# pcbschematics00.net
KiCad netlist of a schematic drawn in EasyEDA
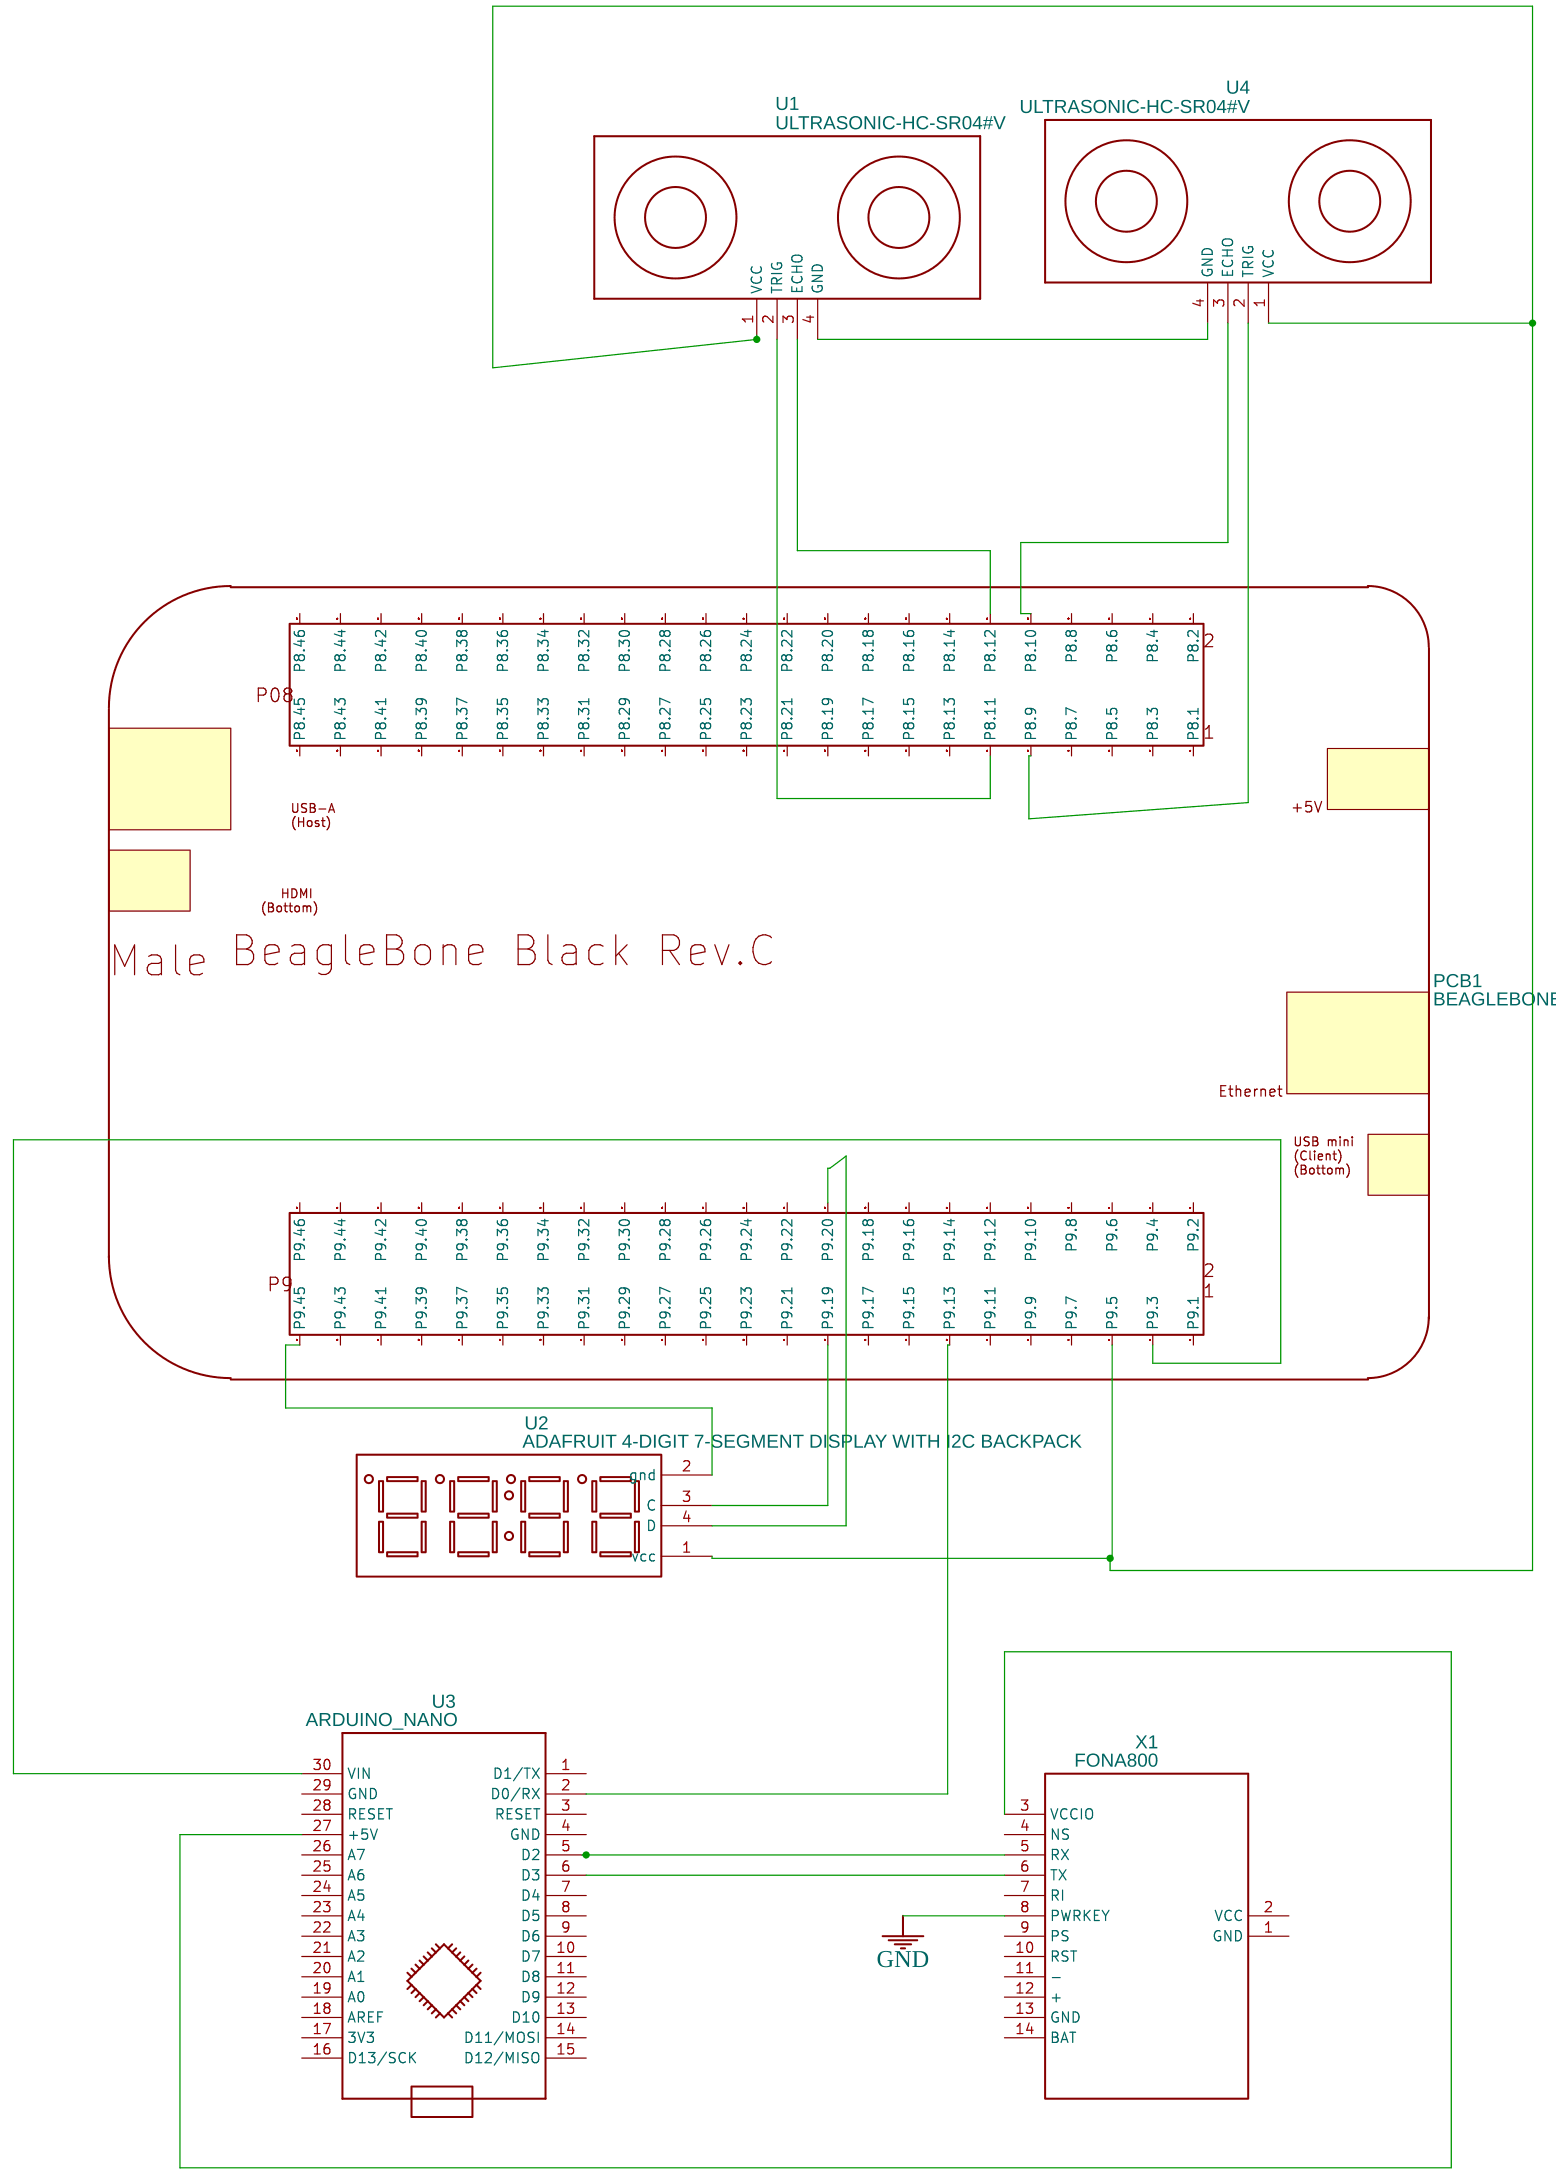
[diagram p0: schematic sheet]

(export (version "E")
  (design (tool "Eeschema 10.0.6"))
  (components
    (comp (ref "PCB1") (value "BEAGLEBONE_BLACK MALE") (libsource (lib "") (part "BEAGLEBONE_BLACK MALE")))
    (comp (ref "U1") (value "ULTRASONIC-HC-SR04#V") (libsource (lib "") (part "ULTRASONIC-HC-SR04#V")))
    (comp (ref "U2")
      (value "ADAFRUIT 4-DIGIT 7-SEGMENT DISPLAY WITH I2C BACKPACK")
      (libsource (lib "") (part "ADAFRUIT 4-DIGIT 7-SEGMENT DISPLAY WITH I2C BACKPACK"))
    )
    (comp (ref "U3") (value "ARDUINO_NANO") (libsource (lib "") (part "ARDUINO_NANO")))
    (comp (ref "U4") (value "ULTRASONIC-HC-SR04#V") (libsource (lib "") (part "ULTRASONIC-HC-SR04#V_1")))
    (comp (ref "X1") (value "FONA800") (libsource (lib "") (part "FONA800")))
  )
  (nets
    (net (code "1") (name "GND") (class "Default")
      (node (ref "X1") (pin "8") (pinfunction "PWRKEY_8") (pintype "unspecified"))
    )
    (net (code "2") (name "Net-(U1-ECHO)") (class "Default")
      (node (ref "PCB1") (pin "P8.12") (pinfunction "P8.12_P8.12") (pintype "bidirectional"))
      (node (ref "U1") (pin "3") (pinfunction "ECHO_3") (pintype "output"))
    )
    (net (code "3") (name "Net-(U1-GND)") (class "Default")
      (node (ref "U1") (pin "4") (pinfunction "GND_4") (pintype "passive"))
      (node (ref "U4") (pin "4") (pinfunction "GND_4") (pintype "passive"))
    )
    (net (code "4") (name "Net-(U1-TRIG)") (class "Default")
      (node (ref "PCB1") (pin "P8.11") (pinfunction "P8.11_P8.11") (pintype "bidirectional"))
      (node (ref "U1") (pin "2") (pinfunction "TRIG_2") (pintype "input"))
    )
    (net (code "5") (name "Net-(U1-VCC)") (class "Default")
      (node (ref "PCB1") (pin "P9.5") (pinfunction "P9.5_P9.5") (pintype "bidirectional"))
      (node (ref "U1") (pin "1") (pinfunction "VCC_1") (pintype "passive"))
      (node (ref "U2") (pin "1") (pinfunction "vcc_1") (pintype "unspecified"))
      (node (ref "U4") (pin "1") (pinfunction "VCC_1") (pintype "passive"))
    )
    (net (code "6") (name "Net-(U2-C)") (class "Default")
      (node (ref "PCB1") (pin "P9.19") (pinfunction "P9.19_P9.19") (pintype "bidirectional"))
      (node (ref "U2") (pin "3") (pinfunction "C_3") (pintype "unspecified"))
    )
    (net (code "7") (name "Net-(U2-D)") (class "Default")
      (node (ref "PCB1") (pin "P9.20") (pinfunction "P9.20_P9.20") (pintype "bidirectional"))
      (node (ref "U2") (pin "4") (pinfunction "D_4") (pintype "unspecified"))
    )
    (net (code "8") (name "Net-(U2-gnd)") (class "Default")
      (node (ref "PCB1") (pin "P9.45") (pinfunction "P9.45_P9.45") (pintype "bidirectional"))
      (node (ref "U2") (pin "2") (pinfunction "gnd_2") (pintype "unspecified"))
    )
    (net (code "9") (name "Net-(U3-+5V)") (class "Default")
      (node (ref "U3") (pin "27") (pinfunction "+5V_27") (pintype "unspecified"))
      (node (ref "X1") (pin "3") (pinfunction "VCCIO_3") (pintype "unspecified"))
    )
    (net (code "10") (name "Net-(U3-D0{slash}RX)") (class "Default")
      (node (ref "PCB1") (pin "P9.13") (pinfunction "P9.13_P9.13") (pintype "bidirectional"))
      (node (ref "U3") (pin "2") (pinfunction "D0/RX_2") (pintype "unspecified"))
    )
    (net (code "11") (name "Net-(U3-D2)") (class "Default")
      (node (ref "U3") (pin "5") (pinfunction "D2_5") (pintype "unspecified"))
      (node (ref "X1") (pin "5") (pinfunction "RX_5") (pintype "unspecified"))
    )
    (net (code "12") (name "Net-(U3-D3)") (class "Default")
      (node (ref "U3") (pin "6") (pinfunction "D3_6") (pintype "unspecified"))
      (node (ref "X1") (pin "6") (pinfunction "TX_6") (pintype "unspecified"))
    )
    (net (code "13") (name "Net-(U3-VIN)") (class "Default")
      (node (ref "PCB1") (pin "P9.3") (pinfunction "P9.3_P9.3") (pintype "bidirectional"))
      (node (ref "U3") (pin "30") (pinfunction "VIN_30") (pintype "unspecified"))
    )
    (net (code "14") (name "Net-(U4-ECHO)") (class "Default")
      (node (ref "PCB1") (pin "P8.10") (pinfunction "P8.10_P8.10") (pintype "bidirectional"))
      (node (ref "U4") (pin "3") (pinfunction "ECHO_3") (pintype "output"))
    )
    (net (code "15") (name "Net-(U4-TRIG)") (class "Default")
      (node (ref "PCB1") (pin "P8.9") (pinfunction "P8.9_P8.9") (pintype "bidirectional"))
      (node (ref "U4") (pin "2") (pinfunction "TRIG_2") (pintype "input"))
    )
    (net (code "16") (name "unconnected-(PCB1-PadP8.1)") (class "Default")
      (node (ref "PCB1") (pin "P8.1") (pinfunction "P8.1_P8.1") (pintype "bidirectional"))
    )
    (net (code "17") (name "unconnected-(PCB1-PadP8.2)") (class "Default")
      (node (ref "PCB1") (pin "P8.2") (pinfunction "P8.2_P8.2") (pintype "bidirectional"))
    )
    (net (code "18") (name "unconnected-(PCB1-PadP8.3)") (class "Default")
      (node (ref "PCB1") (pin "P8.3") (pinfunction "P8.3_P8.3") (pintype "bidirectional"))
    )
    (net (code "19") (name "unconnected-(PCB1-PadP8.4)") (class "Default")
      (node (ref "PCB1") (pin "P8.4") (pinfunction "P8.4_P8.4") (pintype "bidirectional"))
    )
    (net (code "20") (name "unconnected-(PCB1-PadP8.5)") (class "Default")
      (node (ref "PCB1") (pin "P8.5") (pinfunction "P8.5_P8.5") (pintype "bidirectional"))
    )
    (net (code "21") (name "unconnected-(PCB1-PadP8.6)") (class "Default")
      (node (ref "PCB1") (pin "P8.6") (pinfunction "P8.6_P8.6") (pintype "bidirectional"))
    )
    (net (code "22") (name "unconnected-(PCB1-PadP8.7)") (class "Default")
      (node (ref "PCB1") (pin "P8.7") (pinfunction "P8.7_P8.7") (pintype "bidirectional"))
    )
    (net (code "23") (name "unconnected-(PCB1-PadP8.8)") (class "Default")
      (node (ref "PCB1") (pin "P8.8") (pinfunction "P8.8_P8.8") (pintype "bidirectional"))
    )
    (net (code "24") (name "unconnected-(PCB1-PadP8.13)") (class "Default")
      (node (ref "PCB1") (pin "P8.13") (pinfunction "P8.13_P8.13") (pintype "bidirectional"))
    )
    (net (code "25") (name "unconnected-(PCB1-PadP8.14)") (class "Default")
      (node (ref "PCB1") (pin "P8.14") (pinfunction "P8.14_P8.14") (pintype "bidirectional"))
    )
    (net (code "26") (name "unconnected-(PCB1-PadP8.15)") (class "Default")
      (node (ref "PCB1") (pin "P8.15") (pinfunction "P8.15_P8.15") (pintype "bidirectional"))
    )
    (net (code "27") (name "unconnected-(PCB1-PadP8.16)") (class "Default")
      (node (ref "PCB1") (pin "P8.16") (pinfunction "P8.16_P8.16") (pintype "bidirectional"))
    )
    (net (code "28") (name "unconnected-(PCB1-PadP8.17)") (class "Default")
      (node (ref "PCB1") (pin "P8.17") (pinfunction "P8.17_P8.17") (pintype "bidirectional"))
    )
    (net (code "29") (name "unconnected-(PCB1-PadP8.18)") (class "Default")
      (node (ref "PCB1") (pin "P8.18") (pinfunction "P8.18_P8.18") (pintype "bidirectional"))
    )
    (net (code "30") (name "unconnected-(PCB1-PadP8.19)") (class "Default")
      (node (ref "PCB1") (pin "P8.19") (pinfunction "P8.19_P8.19") (pintype "bidirectional"))
    )
    (net (code "31") (name "unconnected-(PCB1-PadP8.20)") (class "Default")
      (node (ref "PCB1") (pin "P8.20") (pinfunction "P8.20_P8.20") (pintype "bidirectional"))
    )
    (net (code "32") (name "unconnected-(PCB1-PadP8.21)") (class "Default")
      (node (ref "PCB1") (pin "P8.21") (pinfunction "P8.21_P8.21") (pintype "bidirectional"))
    )
    (net (code "33") (name "unconnected-(PCB1-PadP8.22)") (class "Default")
      (node (ref "PCB1") (pin "P8.22") (pinfunction "P8.22_P8.22") (pintype "bidirectional"))
    )
    (net (code "34") (name "unconnected-(PCB1-PadP8.23)") (class "Default")
      (node (ref "PCB1") (pin "P8.23") (pinfunction "P8.23_P8.23") (pintype "bidirectional"))
    )
    (net (code "35") (name "unconnected-(PCB1-PadP8.24)") (class "Default")
      (node (ref "PCB1") (pin "P8.24") (pinfunction "P8.24_P8.24") (pintype "bidirectional"))
    )
    (net (code "36") (name "unconnected-(PCB1-PadP8.25)") (class "Default")
      (node (ref "PCB1") (pin "P8.25") (pinfunction "P8.25_P8.25") (pintype "bidirectional"))
    )
    (net (code "37") (name "unconnected-(PCB1-PadP8.26)") (class "Default")
      (node (ref "PCB1") (pin "P8.26") (pinfunction "P8.26_P8.26") (pintype "bidirectional"))
    )
    (net (code "38") (name "unconnected-(PCB1-PadP8.27)") (class "Default")
      (node (ref "PCB1") (pin "P8.27") (pinfunction "P8.27_P8.27") (pintype "bidirectional"))
    )
    (net (code "39") (name "unconnected-(PCB1-PadP8.28)") (class "Default")
      (node (ref "PCB1") (pin "P8.28") (pinfunction "P8.28_P8.28") (pintype "bidirectional"))
    )
    (net (code "40") (name "unconnected-(PCB1-PadP8.29)") (class "Default")
      (node (ref "PCB1") (pin "P8.29") (pinfunction "P8.29_P8.29") (pintype "bidirectional"))
    )
    (net (code "41") (name "unconnected-(PCB1-PadP8.30)") (class "Default")
      (node (ref "PCB1") (pin "P8.30") (pinfunction "P8.30_P8.30") (pintype "bidirectional"))
    )
    (net (code "42") (name "unconnected-(PCB1-PadP8.31)") (class "Default")
      (node (ref "PCB1") (pin "P8.31") (pinfunction "P8.31_P8.31") (pintype "bidirectional"))
    )
    (net (code "43") (name "unconnected-(PCB1-PadP8.32)") (class "Default")
      (node (ref "PCB1") (pin "P8.32") (pinfunction "P8.32_P8.32") (pintype "bidirectional"))
    )
    (net (code "44") (name "unconnected-(PCB1-PadP8.33)") (class "Default")
      (node (ref "PCB1") (pin "P8.33") (pinfunction "P8.33_P8.33") (pintype "bidirectional"))
    )
    (net (code "45") (name "unconnected-(PCB1-PadP8.34)") (class "Default")
      (node (ref "PCB1") (pin "P8.34") (pinfunction "P8.34_P8.34") (pintype "bidirectional"))
    )
    (net (code "46") (name "unconnected-(PCB1-PadP8.35)") (class "Default")
      (node (ref "PCB1") (pin "P8.35") (pinfunction "P8.35_P8.35") (pintype "bidirectional"))
    )
    (net (code "47") (name "unconnected-(PCB1-PadP8.36)") (class "Default")
      (node (ref "PCB1") (pin "P8.36") (pinfunction "P8.36_P8.36") (pintype "bidirectional"))
    )
    (net (code "48") (name "unconnected-(PCB1-PadP8.37)") (class "Default")
      (node (ref "PCB1") (pin "P8.37") (pinfunction "P8.37_P8.37") (pintype "bidirectional"))
    )
    (net (code "49") (name "unconnected-(PCB1-PadP8.38)") (class "Default")
      (node (ref "PCB1") (pin "P8.38") (pinfunction "P8.38_P8.38") (pintype "bidirectional"))
    )
    (net (code "50") (name "unconnected-(PCB1-PadP8.39)") (class "Default")
      (node (ref "PCB1") (pin "P8.39") (pinfunction "P8.39_P8.39") (pintype "bidirectional"))
    )
    (net (code "51") (name "unconnected-(PCB1-PadP8.40)") (class "Default")
      (node (ref "PCB1") (pin "P8.40") (pinfunction "P8.40_P8.40") (pintype "bidirectional"))
    )
    (net (code "52") (name "unconnected-(PCB1-PadP8.41)") (class "Default")
      (node (ref "PCB1") (pin "P8.41") (pinfunction "P8.41_P8.41") (pintype "bidirectional"))
    )
    (net (code "53") (name "unconnected-(PCB1-PadP8.42)") (class "Default")
      (node (ref "PCB1") (pin "P8.42") (pinfunction "P8.42_P8.42") (pintype "bidirectional"))
    )
    (net (code "54") (name "unconnected-(PCB1-PadP8.43)") (class "Default")
      (node (ref "PCB1") (pin "P8.43") (pinfunction "P8.43_P8.43") (pintype "bidirectional"))
    )
    (net (code "55") (name "unconnected-(PCB1-PadP8.44)") (class "Default")
      (node (ref "PCB1") (pin "P8.44") (pinfunction "P8.44_P8.44") (pintype "bidirectional"))
    )
    (net (code "56") (name "unconnected-(PCB1-PadP8.45)") (class "Default")
      (node (ref "PCB1") (pin "P8.45") (pinfunction "P8.45_P8.45") (pintype "bidirectional"))
    )
    (net (code "57") (name "unconnected-(PCB1-PadP8.46)") (class "Default")
      (node (ref "PCB1") (pin "P8.46") (pinfunction "P8.46_P8.46") (pintype "bidirectional"))
    )
    (net (code "58") (name "unconnected-(PCB1-PadP9.1)") (class "Default")
      (node (ref "PCB1") (pin "P9.1") (pinfunction "P9.1_P9.1") (pintype "bidirectional"))
    )
    (net (code "59") (name "unconnected-(PCB1-PadP9.2)") (class "Default")
      (node (ref "PCB1") (pin "P9.2") (pinfunction "P9.2_P9.2") (pintype "bidirectional"))
    )
    (net (code "60") (name "unconnected-(PCB1-PadP9.4)") (class "Default")
      (node (ref "PCB1") (pin "P9.4") (pinfunction "P9.4_P9.4") (pintype "bidirectional"))
    )
    (net (code "61") (name "unconnected-(PCB1-PadP9.6)") (class "Default")
      (node (ref "PCB1") (pin "P9.6") (pinfunction "P9.6_P9.6") (pintype "bidirectional"))
    )
    (net (code "62") (name "unconnected-(PCB1-PadP9.7)") (class "Default")
      (node (ref "PCB1") (pin "P9.7") (pinfunction "P9.7_P9.7") (pintype "bidirectional"))
    )
    (net (code "63") (name "unconnected-(PCB1-PadP9.8)") (class "Default")
      (node (ref "PCB1") (pin "P9.8") (pinfunction "P9.8_P9.8") (pintype "bidirectional"))
    )
    (net (code "64") (name "unconnected-(PCB1-PadP9.9)") (class "Default")
      (node (ref "PCB1") (pin "P9.9") (pinfunction "P9.9_P9.9") (pintype "bidirectional"))
    )
    (net (code "65") (name "unconnected-(PCB1-PadP9.10)") (class "Default")
      (node (ref "PCB1") (pin "P9.10") (pinfunction "P9.10_P9.10") (pintype "bidirectional"))
    )
    (net (code "66") (name "unconnected-(PCB1-PadP9.11)") (class "Default")
      (node (ref "PCB1") (pin "P9.11") (pinfunction "P9.11_P9.11") (pintype "bidirectional"))
    )
    (net (code "67") (name "unconnected-(PCB1-PadP9.12)") (class "Default")
      (node (ref "PCB1") (pin "P9.12") (pinfunction "P9.12_P9.12") (pintype "bidirectional"))
    )
    (net (code "68") (name "unconnected-(PCB1-PadP9.14)") (class "Default")
      (node (ref "PCB1") (pin "P9.14") (pinfunction "P9.14_P9.14") (pintype "bidirectional"))
    )
    (net (code "69") (name "unconnected-(PCB1-PadP9.15)") (class "Default")
      (node (ref "PCB1") (pin "P9.15") (pinfunction "P9.15_P9.15") (pintype "bidirectional"))
    )
    (net (code "70") (name "unconnected-(PCB1-PadP9.16)") (class "Default")
      (node (ref "PCB1") (pin "P9.16") (pinfunction "P9.16_P9.16") (pintype "bidirectional"))
    )
    (net (code "71") (name "unconnected-(PCB1-PadP9.17)") (class "Default")
      (node (ref "PCB1") (pin "P9.17") (pinfunction "P9.17_P9.17") (pintype "bidirectional"))
    )
    (net (code "72") (name "unconnected-(PCB1-PadP9.18)") (class "Default")
      (node (ref "PCB1") (pin "P9.18") (pinfunction "P9.18_P9.18") (pintype "bidirectional"))
    )
    (net (code "73") (name "unconnected-(PCB1-PadP9.21)") (class "Default")
      (node (ref "PCB1") (pin "P9.21") (pinfunction "P9.21_P9.21") (pintype "bidirectional"))
    )
    (net (code "74") (name "unconnected-(PCB1-PadP9.22)") (class "Default")
      (node (ref "PCB1") (pin "P9.22") (pinfunction "P9.22_P9.22") (pintype "bidirectional"))
    )
    (net (code "75") (name "unconnected-(PCB1-PadP9.23)") (class "Default")
      (node (ref "PCB1") (pin "P9.23") (pinfunction "P9.23_P9.23") (pintype "bidirectional"))
    )
    (net (code "76") (name "unconnected-(PCB1-PadP9.24)") (class "Default")
      (node (ref "PCB1") (pin "P9.24") (pinfunction "P9.24_P9.24") (pintype "bidirectional"))
    )
    (net (code "77") (name "unconnected-(PCB1-PadP9.25)") (class "Default")
      (node (ref "PCB1") (pin "P9.25") (pinfunction "P9.25_P9.25") (pintype "bidirectional"))
    )
    (net (code "78") (name "unconnected-(PCB1-PadP9.26)") (class "Default")
      (node (ref "PCB1") (pin "P9.26") (pinfunction "P9.26_P9.26") (pintype "bidirectional"))
    )
    (net (code "79") (name "unconnected-(PCB1-PadP9.27)") (class "Default")
      (node (ref "PCB1") (pin "P9.27") (pinfunction "P9.27_P9.27") (pintype "bidirectional"))
    )
    (net (code "80") (name "unconnected-(PCB1-PadP9.28)") (class "Default")
      (node (ref "PCB1") (pin "P9.28") (pinfunction "P9.28_P9.28") (pintype "bidirectional"))
    )
    (net (code "81") (name "unconnected-(PCB1-PadP9.29)") (class "Default")
      (node (ref "PCB1") (pin "P9.29") (pinfunction "P9.29_P9.29") (pintype "bidirectional"))
    )
    (net (code "82") (name "unconnected-(PCB1-PadP9.30)") (class "Default")
      (node (ref "PCB1") (pin "P9.30") (pinfunction "P9.30_P9.30") (pintype "bidirectional"))
    )
    (net (code "83") (name "unconnected-(PCB1-PadP9.31)") (class "Default")
      (node (ref "PCB1") (pin "P9.31") (pinfunction "P9.31_P9.31") (pintype "bidirectional"))
    )
    (net (code "84") (name "unconnected-(PCB1-PadP9.32)") (class "Default")
      (node (ref "PCB1") (pin "P9.32") (pinfunction "P9.32_P9.32") (pintype "bidirectional"))
    )
    (net (code "85") (name "unconnected-(PCB1-PadP9.33)") (class "Default")
      (node (ref "PCB1") (pin "P9.33") (pinfunction "P9.33_P9.33") (pintype "bidirectional"))
    )
    (net (code "86") (name "unconnected-(PCB1-PadP9.34)") (class "Default")
      (node (ref "PCB1") (pin "P9.34") (pinfunction "P9.34_P9.34") (pintype "bidirectional"))
    )
    (net (code "87") (name "unconnected-(PCB1-PadP9.35)") (class "Default")
      (node (ref "PCB1") (pin "P9.35") (pinfunction "P9.35_P9.35") (pintype "bidirectional"))
    )
    (net (code "88") (name "unconnected-(PCB1-PadP9.36)") (class "Default")
      (node (ref "PCB1") (pin "P9.36") (pinfunction "P9.36_P9.36") (pintype "bidirectional"))
    )
    (net (code "89") (name "unconnected-(PCB1-PadP9.37)") (class "Default")
      (node (ref "PCB1") (pin "P9.37") (pinfunction "P9.37_P9.37") (pintype "bidirectional"))
    )
    (net (code "90") (name "unconnected-(PCB1-PadP9.38)") (class "Default")
      (node (ref "PCB1") (pin "P9.38") (pinfunction "P9.38_P9.38") (pintype "bidirectional"))
    )
    (net (code "91") (name "unconnected-(PCB1-PadP9.39)") (class "Default")
      (node (ref "PCB1") (pin "P9.39") (pinfunction "P9.39_P9.39") (pintype "bidirectional"))
    )
    (net (code "92") (name "unconnected-(PCB1-PadP9.40)") (class "Default")
      (node (ref "PCB1") (pin "P9.40") (pinfunction "P9.40_P9.40") (pintype "bidirectional"))
    )
    (net (code "93") (name "unconnected-(PCB1-PadP9.41)") (class "Default")
      (node (ref "PCB1") (pin "P9.41") (pinfunction "P9.41_P9.41") (pintype "bidirectional"))
    )
    (net (code "94") (name "unconnected-(PCB1-PadP9.42)") (class "Default")
      (node (ref "PCB1") (pin "P9.42") (pinfunction "P9.42_P9.42") (pintype "bidirectional"))
    )
    (net (code "95") (name "unconnected-(PCB1-PadP9.43)") (class "Default")
      (node (ref "PCB1") (pin "P9.43") (pinfunction "P9.43_P9.43") (pintype "bidirectional"))
    )
    (net (code "96") (name "unconnected-(PCB1-PadP9.44)") (class "Default")
      (node (ref "PCB1") (pin "P9.44") (pinfunction "P9.44_P9.44") (pintype "bidirectional"))
    )
    (net (code "97") (name "unconnected-(PCB1-PadP9.46)") (class "Default")
      (node (ref "PCB1") (pin "P9.46") (pinfunction "P9.46_P9.46") (pintype "bidirectional"))
    )
    (net (code "98") (name "unconnected-(U3-3V3-Pad17)") (class "Default")
      (node (ref "U3") (pin "17") (pinfunction "3V3_17") (pintype "unspecified"))
    )
    (net (code "99") (name "unconnected-(U3-A0-Pad19)") (class "Default")
      (node (ref "U3") (pin "19") (pinfunction "A0_19") (pintype "unspecified"))
    )
    (net (code "100") (name "unconnected-(U3-A1-Pad20)") (class "Default")
      (node (ref "U3") (pin "20") (pinfunction "A1_20") (pintype "unspecified"))
    )
    (net (code "101") (name "unconnected-(U3-A2-Pad21)") (class "Default")
      (node (ref "U3") (pin "21") (pinfunction "A2_21") (pintype "unspecified"))
    )
    (net (code "102") (name "unconnected-(U3-A3-Pad22)") (class "Default")
      (node (ref "U3") (pin "22") (pinfunction "A3_22") (pintype "unspecified"))
    )
    (net (code "103") (name "unconnected-(U3-A4-Pad23)") (class "Default")
      (node (ref "U3") (pin "23") (pinfunction "A4_23") (pintype "unspecified"))
    )
    (net (code "104") (name "unconnected-(U3-A5-Pad24)") (class "Default")
      (node (ref "U3") (pin "24") (pinfunction "A5_24") (pintype "unspecified"))
    )
    (net (code "105") (name "unconnected-(U3-A6-Pad25)") (class "Default")
      (node (ref "U3") (pin "25") (pinfunction "A6_25") (pintype "unspecified"))
    )
    (net (code "106") (name "unconnected-(U3-A7-Pad26)") (class "Default")
      (node (ref "U3") (pin "26") (pinfunction "A7_26") (pintype "unspecified"))
    )
    (net (code "107") (name "unconnected-(U3-AREF-Pad18)") (class "Default")
      (node (ref "U3") (pin "18") (pinfunction "AREF_18") (pintype "unspecified"))
    )
    (net (code "108") (name "unconnected-(U3-D1{slash}TX-Pad1)") (class "Default")
      (node (ref "U3") (pin "1") (pinfunction "D1/TX_1") (pintype "unspecified"))
    )
    (net (code "109") (name "unconnected-(U3-D4-Pad7)") (class "Default")
      (node (ref "U3") (pin "7") (pinfunction "D4_7") (pintype "unspecified"))
    )
    (net (code "110") (name "unconnected-(U3-D5-Pad8)") (class "Default")
      (node (ref "U3") (pin "8") (pinfunction "D5_8") (pintype "unspecified"))
    )
    (net (code "111") (name "unconnected-(U3-D6-Pad9)") (class "Default")
      (node (ref "U3") (pin "9") (pinfunction "D6_9") (pintype "unspecified"))
    )
    (net (code "112") (name "unconnected-(U3-D7-Pad10)") (class "Default")
      (node (ref "U3") (pin "10") (pinfunction "D7_10") (pintype "unspecified"))
    )
    (net (code "113") (name "unconnected-(U3-D8-Pad11)") (class "Default")
      (node (ref "U3") (pin "11") (pinfunction "D8_11") (pintype "unspecified"))
    )
    (net (code "114") (name "unconnected-(U3-D9-Pad12)") (class "Default")
      (node (ref "U3") (pin "12") (pinfunction "D9_12") (pintype "unspecified"))
    )
    (net (code "115") (name "unconnected-(U3-D10-Pad13)") (class "Default")
      (node (ref "U3") (pin "13") (pinfunction "D10_13") (pintype "unspecified"))
    )
    (net (code "116") (name "unconnected-(U3-D11{slash}MOSI-Pad14)") (class "Default")
      (node (ref "U3") (pin "14") (pinfunction "D11/MOSI_14") (pintype "unspecified"))
    )
    (net (code "117") (name "unconnected-(U3-D12{slash}MISO-Pad15)") (class "Default")
      (node (ref "U3") (pin "15") (pinfunction "D12/MISO_15") (pintype "unspecified"))
    )
    (net (code "118") (name "unconnected-(U3-D13{slash}SCK-Pad16)") (class "Default")
      (node (ref "U3") (pin "16") (pinfunction "D13/SCK_16") (pintype "unspecified"))
    )
    (net (code "119") (name "unconnected-(U3-GND-Pad4)") (class "Default")
      (node (ref "U3") (pin "4") (pinfunction "GND_4") (pintype "unspecified"))
    )
    (net (code "120") (name "unconnected-(U3-GND-Pad29)") (class "Default")
      (node (ref "U3") (pin "29") (pinfunction "GND_29") (pintype "unspecified"))
    )
    (net (code "121") (name "unconnected-(U3-RESET-Pad3)") (class "Default")
      (node (ref "U3") (pin "3") (pinfunction "RESET_3") (pintype "unspecified"))
    )
    (net (code "122") (name "unconnected-(U3-RESET-Pad28)") (class "Default")
      (node (ref "U3") (pin "28") (pinfunction "RESET_28") (pintype "unspecified"))
    )
    (net (code "123") (name "unconnected-(X1-+-Pad12)") (class "Default")
      (node (ref "X1") (pin "12") (pinfunction "+_12") (pintype "unspecified"))
    )
    (net (code "124") (name "unconnected-(X1---Pad11)") (class "Default")
      (node (ref "X1") (pin "11") (pinfunction "-_11") (pintype "unspecified"))
    )
    (net (code "125") (name "unconnected-(X1-BAT-Pad14)") (class "Default")
      (node (ref "X1") (pin "14") (pinfunction "BAT_14") (pintype "unspecified"))
    )
    (net (code "126") (name "unconnected-(X1-GND-Pad1)") (class "Default")
      (node (ref "X1") (pin "1") (pinfunction "GND_1") (pintype "unspecified"))
    )
    (net (code "127") (name "unconnected-(X1-GND-Pad13)") (class "Default")
      (node (ref "X1") (pin "13") (pinfunction "GND_13") (pintype "unspecified"))
    )
    (net (code "128") (name "unconnected-(X1-NS-Pad4)") (class "Default")
      (node (ref "X1") (pin "4") (pinfunction "NS_4") (pintype "unspecified"))
    )
    (net (code "129") (name "unconnected-(X1-PS-Pad9)") (class "Default")
      (node (ref "X1") (pin "9") (pinfunction "PS_9") (pintype "unspecified"))
    )
    (net (code "130") (name "unconnected-(X1-RI-Pad7)") (class "Default")
      (node (ref "X1") (pin "7") (pinfunction "RI_7") (pintype "unspecified"))
    )
    (net (code "131") (name "unconnected-(X1-RST-Pad10)") (class "Default")
      (node (ref "X1") (pin "10") (pinfunction "RST_10") (pintype "unspecified"))
    )
    (net (code "132") (name "unconnected-(X1-VCC-Pad2)") (class "Default")
      (node (ref "X1") (pin "2") (pinfunction "VCC_2") (pintype "unspecified"))
    )
  )
)
